# chicker.net
KiCad netlist of a schematic drawn in Altium Designer
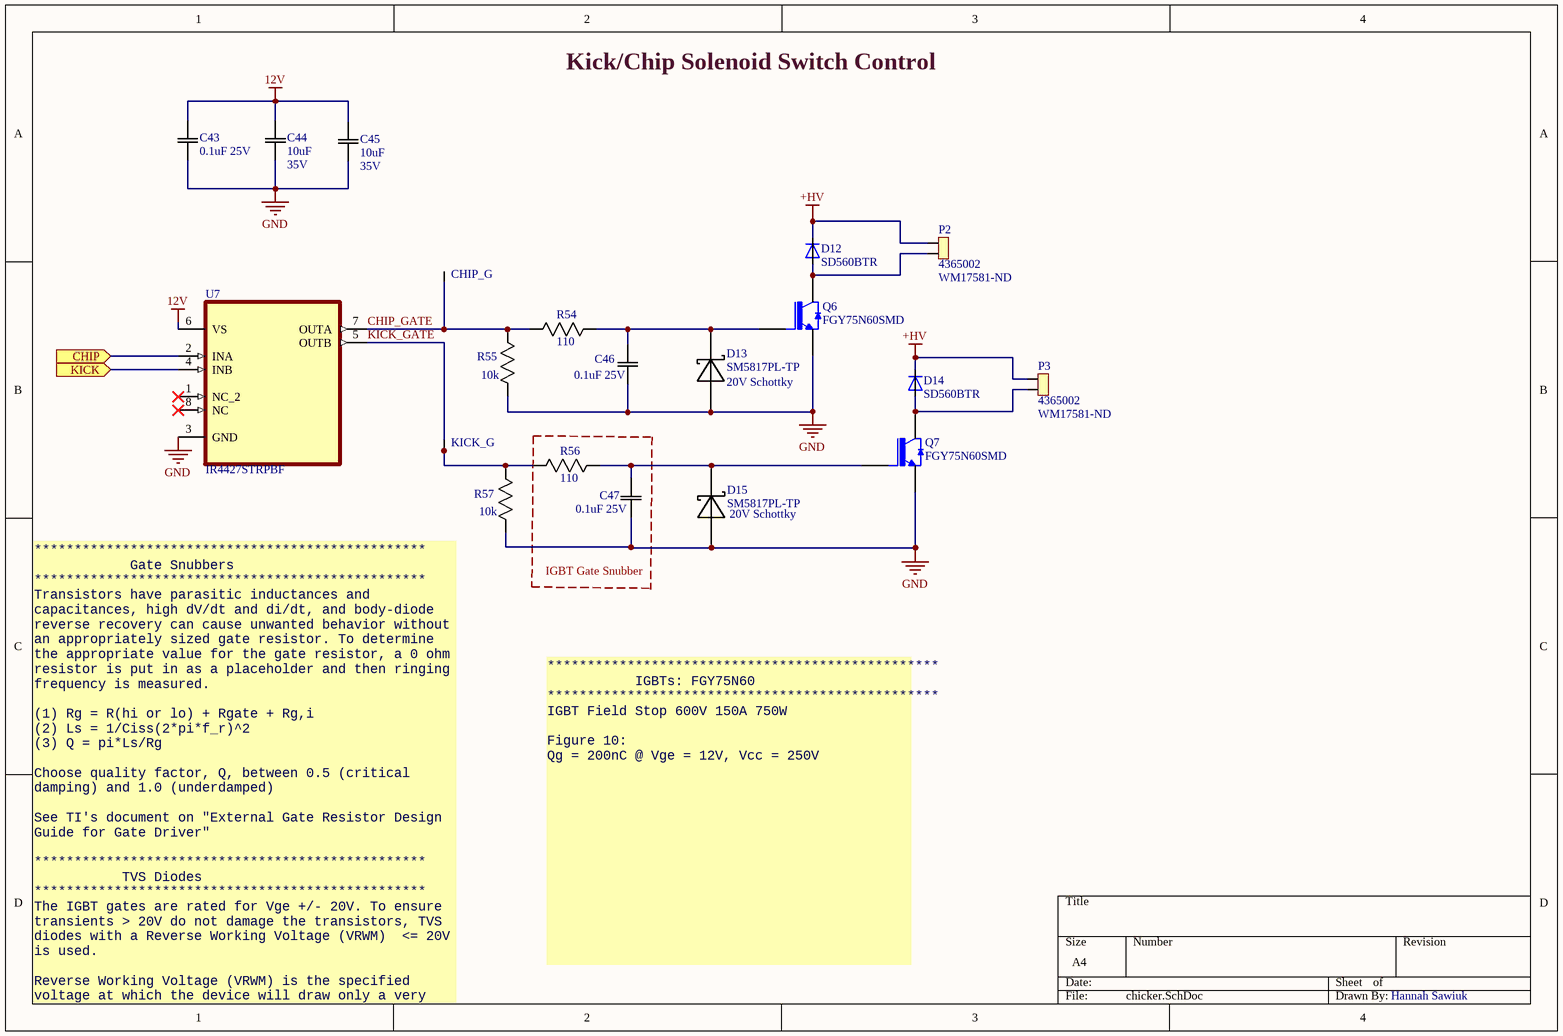
[diagram p0: chicker.SchDoc]

(export (version "E")
  (design (tool "Eeschema 10.0.6"))
  (components
    (comp (ref "C43")
      (value "0.1uF 25V")
      (footprint "0805")
      (description "CAP CER 0.1UF 25V X7R 0805")
      (fields (field (name "TOLERANCE") "10%"))
      (libsource (lib "AltiumLibraries") (part "CAP 0.1uF 25V"))
    )
    (comp (ref "C44")
      (value "10uF")
      (footprint "0805")
      (description "CAP CER 10UF 35V X7R 0805")
      (fields (field (name "TOLERANCE") "10%") (field (name "RATING") "35V"))
      (libsource (lib "AltiumLibraries") (part "CAP 10uF 35V"))
    )
    (comp (ref "C45")
      (value "10uF")
      (footprint "0805")
      (description "CAP CER 10UF 35V X7R 0805")
      (fields (field (name "TOLERANCE") "10%") (field (name "RATING") "35V"))
      (libsource (lib "AltiumLibraries") (part "CAP 10uF 35V"))
    )
    (comp (ref "C46")
      (value "0.1uF 25V")
      (footprint "0805")
      (description "CAP CER 0.1UF 25V X7R 0805")
      (fields (field (name "TOLERANCE") "10%"))
      (libsource (lib "") (part "CAP 0.1uF 25V_1"))
    )
    (comp (ref "C47")
      (value "0.1uF 25V")
      (footprint "0805")
      (description "CAP CER 0.1UF 25V X7R 0805")
      (fields (field (name "TOLERANCE") "10%"))
      (libsource (lib "") (part "CAP 0.1uF 25V_1"))
    )
    (comp (ref "CHIP_G")
      (value "Test Point (Via)")
      (footprint "TP")
      (libsource (lib "AltiumLibraries") (part "Test Point (Via)"))
    )
    (comp (ref "D12")
      (value "SD560BTR")
      (footprint "DO-214AA")
      (description "Diode Standard 600V 5A Surface Mount SMB")
      (libsource (lib "AltiumLibraries") (part "DIODE STANDARD 600V 5A"))
    )
    (comp (ref "D13")
      (value "SM5817PL-TP")
      (footprint "SOD-123")
      (description "Diode Schottky 20V 1A Surface Mount SOD-123FL")
      (fields (field (name "MF") "Micro Commercial Co"))
      (libsource (lib "AltiumLibraries") (part "DIODE SCHOTTKY 20V 1A"))
    )
    (comp (ref "D14")
      (value "SD560BTR")
      (footprint "DO-214AA")
      (description "Diode Standard 600V 5A Surface Mount SMB")
      (libsource (lib "AltiumLibraries") (part "DIODE STANDARD 600V 5A"))
    )
    (comp (ref "D15")
      (value "SM5817PL-TP")
      (footprint "SOD-123")
      (description "Diode Schottky 20V 1A Surface Mount SOD-123FL")
      (fields (field (name "MF") "Micro Commercial Co"))
      (libsource (lib "AltiumLibraries") (part "DIODE SCHOTTKY 20V 1A"))
    )
    (comp (ref "KICK_G")
      (value "Test Point (Via)")
      (footprint "TP")
      (libsource (lib "AltiumLibraries") (part "Test Point (Via)"))
    )
    (comp (ref "P2")
      (value "4365002")
      (footprint "43650-02")
      (description "MOLEX MICROFIT 2CKT RIGHT THRU")
      (fields
        (field (name "MF") "MOLEX")
        (field (name "MP") "4365002XX")
        (field (name "SUPPLIER PART NUMBER 2") "WM17581-ND")
      )
      (libsource (lib "AltiumLibraries") (part "CN MOLEX 4365002XX"))
    )
    (comp (ref "P3")
      (value "4365002")
      (footprint "43650-02")
      (description "MOLEX MICROFIT 2CKT RIGHT THRU")
      (fields
        (field (name "MF") "MOLEX")
        (field (name "MP") "4365002XX")
        (field (name "SUPPLIER PART NUMBER 2") "WM17581-ND")
      )
      (libsource (lib "AltiumLibraries") (part "CN MOLEX 4365002XX"))
    )
    (comp (ref "Q6")
      (value "FGY75N60SMD")
      (footprint "TO-247-3")
      (description "IGBT Field Stop 600V 150A 750W Through Hole PowerTO-247-3")
      (fields (field (name "MF") "ON Semiconductor") (field (name "POWER") "750W"))
      (libsource (lib "AltiumLibraries") (part "FGY75N60SMD"))
    )
    (comp (ref "Q7")
      (value "FGY75N60SMD")
      (footprint "TO-247-3")
      (description "IGBT Field Stop 600V 150A 750W Through Hole PowerTO-247-3")
      (fields (field (name "MF") "ON Semiconductor") (field (name "POWER") "750W"))
      (libsource (lib "AltiumLibraries") (part "FGY75N60SMD"))
    )
    (comp (ref "R54")
      (value "110")
      (footprint "0805")
      (description "RES SMD 110 OHM 1% 1/8W 0805")
      (fields (field (name "TOLERANCE") "1%"))
      (libsource (lib "AltiumLibraries") (part "RES 110.0 1/8W - 1%"))
    )
    (comp (ref "R55")
      (value "10k")
      (footprint "0805")
      (description "RES SMD 10K OHM 1% 1/8W 0805")
      (fields (field (name "TOLERANCE") "1%"))
      (libsource (lib "AltiumLibraries") (part "RES 10k 1/8W - 1%"))
    )
    (comp (ref "R56")
      (value "110")
      (footprint "0805")
      (description "RES SMD 110 OHM 1% 1/8W 0805")
      (fields (field (name "TOLERANCE") "1%"))
      (libsource (lib "") (part "RES 110.0 1/8W - 1%_1"))
    )
    (comp (ref "R57")
      (value "10k")
      (footprint "0805")
      (description "RES SMD 10K OHM 1% 1/8W 0805")
      (fields (field (name "TOLERANCE") "1%"))
      (libsource (lib "AltiumLibraries") (part "RES 10k 1/8W - 1%"))
    )
    (comp (ref "U7")
      (value "IR4427STRPBF")
      (footprint "8-SOIC")
      (description "Low-Side Gate Driver IC Non-Inverting 8-SOIC")
      (fields (field (name "MF") "Infineon Technologies"))
      (libsource (lib "AltiumLibraries") (part "IR4427STRPBF"))
    )
  )
  (nets
    (net (code "1") (name "+HV") (class "Default")
      (node (ref "D12") (pin "C") (pinfunction "C_C") (pintype "passive"))
      (node (ref "D14") (pin "C") (pinfunction "C_C") (pintype "passive"))
      (node (ref "P2") (pin "1") (pinfunction "1_1") (pintype "passive"))
      (node (ref "P3") (pin "1") (pinfunction "1_1") (pintype "passive"))
    )
    (net (code "2") (name "/CHIP") (class "Default")
      (node (ref "U7") (pin "2") (pinfunction "INA_2") (pintype "input"))
    )
    (net (code "3") (name "/CHIP_GATE") (class "Default")
      (node (ref "CHIP_G") (pin "1") (pinfunction "1_1") (pintype "passive"))
      (node (ref "R54") (pin "2") (pinfunction "R2_2") (pintype "passive"))
      (node (ref "R55") (pin "1") (pinfunction "R1_1") (pintype "passive"))
      (node (ref "U7") (pin "7") (pinfunction "OUTA_7") (pintype "output"))
    )
    (net (code "4") (name "/KICK") (class "Default")
      (node (ref "U7") (pin "4") (pinfunction "INB_4") (pintype "input"))
    )
    (net (code "5") (name "/KICK_GATE") (class "Default")
      (node (ref "KICK_G") (pin "1") (pinfunction "1_1") (pintype "passive"))
      (node (ref "R56") (pin "2") (pinfunction "R2_2") (pintype "passive"))
      (node (ref "R57") (pin "1") (pinfunction "R1_1") (pintype "passive"))
      (node (ref "U7") (pin "5") (pinfunction "OUTB_5") (pintype "output"))
    )
    (net (code "6") (name "12V") (class "Default")
      (node (ref "C43") (pin "2") (pinfunction "C2_2") (pintype "passive"))
      (node (ref "C44") (pin "1") (pinfunction "C1_1") (pintype "passive"))
      (node (ref "C45") (pin "1") (pinfunction "C1_1") (pintype "passive"))
      (node (ref "U7") (pin "6") (pinfunction "VS_6") (pintype "power_in"))
    )
    (net (code "7") (name "GND") (class "Default")
      (node (ref "C43") (pin "1") (pinfunction "C1_1") (pintype "passive"))
      (node (ref "C44") (pin "2") (pinfunction "C2_2") (pintype "passive"))
      (node (ref "C45") (pin "2") (pinfunction "C2_2") (pintype "passive"))
      (node (ref "C46") (pin "1") (pinfunction "C1_1") (pintype "passive"))
      (node (ref "C47") (pin "1") (pinfunction "C1_1") (pintype "passive"))
      (node (ref "D13") (pin "A") (pinfunction "A_A") (pintype "passive"))
      (node (ref "D15") (pin "A") (pinfunction "A_A") (pintype "passive"))
      (node (ref "Q6") (pin "3") (pinfunction "E_3") (pintype "passive"))
      (node (ref "Q7") (pin "3") (pinfunction "E_3") (pintype "passive"))
      (node (ref "R55") (pin "2") (pinfunction "R2_2") (pintype "passive"))
      (node (ref "R57") (pin "2") (pinfunction "R2_2") (pintype "passive"))
      (node (ref "U7") (pin "3") (pinfunction "GND_3") (pintype "passive"))
    )
    (net (code "8") (name "Net-(C46-C2)") (class "Default")
      (node (ref "C46") (pin "2") (pinfunction "C2_2") (pintype "passive"))
      (node (ref "D13") (pin "C") (pinfunction "K_C") (pintype "passive"))
      (node (ref "Q6") (pin "1") (pinfunction "G_1") (pintype "passive"))
      (node (ref "R54") (pin "1") (pinfunction "R1_1") (pintype "passive"))
    )
    (net (code "9") (name "Net-(C47-C2)") (class "Default")
      (node (ref "C47") (pin "2") (pinfunction "C2_2") (pintype "passive"))
      (node (ref "D15") (pin "C") (pinfunction "K_C") (pintype "passive"))
      (node (ref "Q7") (pin "1") (pinfunction "G_1") (pintype "passive"))
      (node (ref "R56") (pin "1") (pinfunction "R1_1") (pintype "passive"))
    )
    (net (code "10") (name "Net-(Q6-C)") (class "Default")
      (node (ref "D12") (pin "A") (pinfunction "A_A") (pintype "passive"))
      (node (ref "P2") (pin "2") (pinfunction "2_2") (pintype "passive"))
      (node (ref "Q6") (pin "2") (pinfunction "C_2") (pintype "passive"))
    )
    (net (code "11") (name "Net-(Q7-C)") (class "Default")
      (node (ref "D14") (pin "A") (pinfunction "A_A") (pintype "passive"))
      (node (ref "P3") (pin "2") (pinfunction "2_2") (pintype "passive"))
      (node (ref "Q7") (pin "2") (pinfunction "C_2") (pintype "passive"))
    )
    (net (code "12") (name "unconnected-(U7-NC-Pad8)") (class "Default")
      (node (ref "U7") (pin "8") (pinfunction "NC_8") (pintype "input+no_connect"))
    )
    (net (code "13") (name "unconnected-(U7-NC_2-Pad1)") (class "Default")
      (node (ref "U7") (pin "1") (pinfunction "NC_2_1") (pintype "input+no_connect"))
    )
  )
)
